# IO.net
KiCad netlist of a schematic drawn in Altium Designer
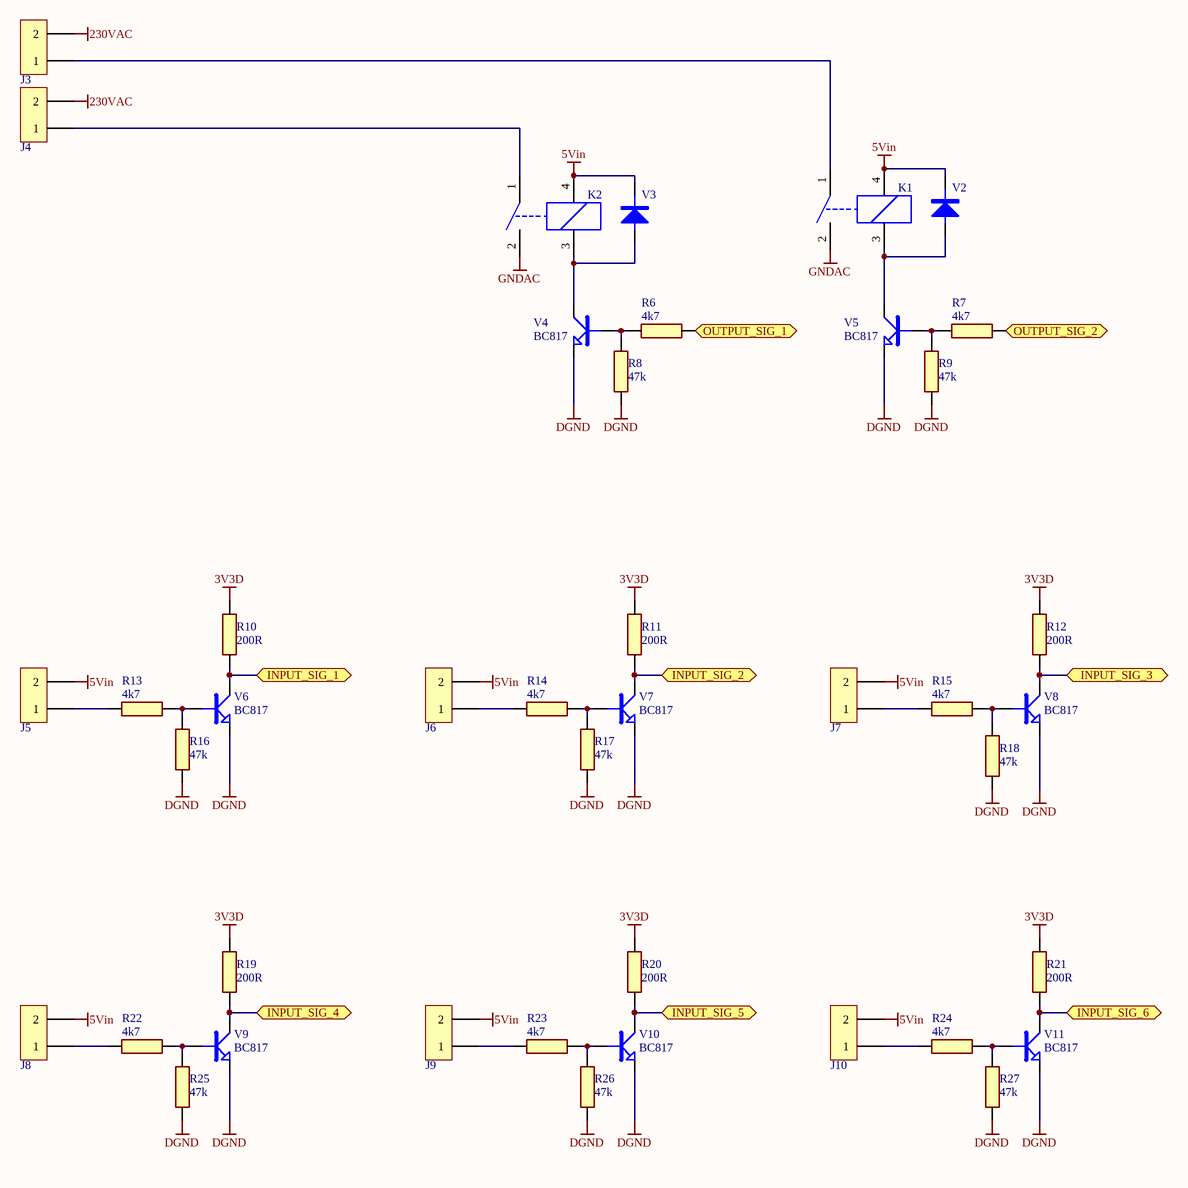
[diagram p0: IO.SchDoc]

(export (version "E")
  (design (tool "Eeschema 10.0.6"))
  (components
    (comp (ref "J3")
      (value "CON2")
      (footprint "CON-MSTB-5.08-2p")
      (description "2 pole connector")
      (libsource (lib "Moj_Lib") (part "CON2"))
    )
    (comp (ref "J4")
      (value "CON2")
      (footprint "CON-MSTB-5.08-2p")
      (description "2 pole connector")
      (libsource (lib "Moj_Lib") (part "CON2"))
    )
    (comp (ref "J5")
      (value "CON2")
      (footprint "CON-MSTB-5.08-2p")
      (description "2 pole connector")
      (libsource (lib "Moj_Lib") (part "CON2"))
    )
    (comp (ref "J6")
      (value "CON2")
      (footprint "CON-MSTB-5.08-2p")
      (description "2 pole connector")
      (libsource (lib "Moj_Lib") (part "CON2"))
    )
    (comp (ref "J7")
      (value "CON2")
      (footprint "CON-MSTB-5.08-2p")
      (description "2 pole connector")
      (libsource (lib "Moj_Lib") (part "CON2"))
    )
    (comp (ref "J8")
      (value "CON2")
      (footprint "CON-MSTB-5.08-2p")
      (description "2 pole connector")
      (libsource (lib "Moj_Lib") (part "CON2"))
    )
    (comp (ref "J9")
      (value "CON2")
      (footprint "CON-MSTB-5.08-2p")
      (description "2 pole connector")
      (libsource (lib "Moj_Lib") (part "CON2"))
    )
    (comp (ref "J10")
      (value "CON2")
      (footprint "CON-MSTB-5.08-2p")
      (description "2 pole connector")
      (libsource (lib "Moj_Lib") (part "CON2"))
    )
    (comp (ref "K1")
      (value "RELAY-HF49FD_012-1H12F")
      (footprint "RELAY-HF49FD_012-1H12F")
      (description "Relay")
      (libsource (lib "Moj_lib") (part "RELAY-HF49FD_012-1H12F"))
    )
    (comp (ref "K2")
      (value "RELAY-HF49FD_012-1H12F")
      (footprint "RELAY-HF49FD_012-1H12F")
      (description "Relay")
      (libsource (lib "Moj_lib") (part "RELAY-HF49FD_012-1H12F"))
    )
    (comp (ref "R6")
      (value "4k7")
      (footprint "RES_0805_SMD")
      (description "0805")
      (libsource (lib "") (part "RES_1"))
    )
    (comp (ref "R7")
      (value "4k7")
      (footprint "RES_0805_SMD")
      (description "0805")
      (libsource (lib "") (part "RES_3"))
    )
    (comp (ref "R8")
      (value "47k")
      (footprint "RES_0805_SMD")
      (description "0805")
      (libsource (lib "") (part "RES_2"))
    )
    (comp (ref "R9")
      (value "47k")
      (footprint "RES_0805_SMD")
      (description "0805")
      (libsource (lib "") (part "RES_2"))
    )
    (comp (ref "R10")
      (value "200R")
      (footprint "RES_0805_SMD")
      (description "0805")
      (libsource (lib "") (part "RES_2"))
    )
    (comp (ref "R11")
      (value "200R")
      (footprint "RES_0805_SMD")
      (description "0805")
      (libsource (lib "") (part "RES_2"))
    )
    (comp (ref "R12")
      (value "200R")
      (footprint "RES_0805_SMD")
      (description "0805")
      (libsource (lib "") (part "RES_2"))
    )
    (comp (ref "R13")
      (value "4k7")
      (footprint "RES_0805_SMD")
      (description "0805")
      (libsource (lib "") (part "RES_1"))
    )
    (comp (ref "R14")
      (value "4k7")
      (footprint "RES_0805_SMD")
      (description "0805")
      (libsource (lib "") (part "RES_1"))
    )
    (comp (ref "R15")
      (value "4k7")
      (footprint "RES_0805_SMD")
      (description "0805")
      (libsource (lib "") (part "RES_1"))
    )
    (comp (ref "R16")
      (value "47k")
      (footprint "RES_0805_SMD")
      (description "0805")
      (libsource (lib "") (part "RES_2"))
    )
    (comp (ref "R17")
      (value "47k")
      (footprint "RES_0805_SMD")
      (description "0805")
      (libsource (lib "Moj_lib") (part "RES"))
    )
    (comp (ref "R18")
      (value "47k")
      (footprint "RES_0805_SMD")
      (description "0805")
      (libsource (lib "") (part "RES_2"))
    )
    (comp (ref "R19")
      (value "200R")
      (footprint "RES_0805_SMD")
      (description "0805")
      (libsource (lib "") (part "RES_2"))
    )
    (comp (ref "R20")
      (value "200R")
      (footprint "RES_0805_SMD")
      (description "0805")
      (libsource (lib "") (part "RES_2"))
    )
    (comp (ref "R21")
      (value "200R")
      (footprint "RES_0805_SMD")
      (description "0805")
      (libsource (lib "") (part "RES_2"))
    )
    (comp (ref "R22")
      (value "4k7")
      (footprint "RES_0805_SMD")
      (description "0805")
      (libsource (lib "") (part "RES_3"))
    )
    (comp (ref "R23")
      (value "4k7")
      (footprint "RES_0805_SMD")
      (description "0805")
      (libsource (lib "") (part "RES_1"))
    )
    (comp (ref "R24")
      (value "4k7")
      (footprint "RES_0805_SMD")
      (description "0805")
      (libsource (lib "") (part "RES_3"))
    )
    (comp (ref "R25")
      (value "47k")
      (footprint "RES_0805_SMD")
      (description "0805")
      (libsource (lib "Moj_lib") (part "RES"))
    )
    (comp (ref "R26")
      (value "47k")
      (footprint "RES_0805_SMD")
      (description "0805")
      (libsource (lib "") (part "RES_2"))
    )
    (comp (ref "R27")
      (value "47k")
      (footprint "RES_0805_SMD")
      (description "0805")
      (libsource (lib "Moj_lib") (part "RES"))
    )
    (comp (ref "V2")
      (value "DIODE")
      (footprint "DIODE-0.4_H")
      (description "Trough hole diode")
      (libsource (lib "ShemaLibrary_IEL") (part "DIODE"))
    )
    (comp (ref "V3")
      (value "DIODE")
      (footprint "DIODE-0.4_H")
      (description "Trough hole diode")
      (libsource (lib "ShemaLibrary_IEL") (part "DIODE"))
    )
    (comp (ref "V4")
      (value "BC817")
      (footprint "SOT-23_P")
      (description "NPN tranzistor BC-817")
      (libsource (lib "ShemaLibrary_IEL") (part "BC817"))
    )
    (comp (ref "V5")
      (value "BC817")
      (footprint "SOT-23_P")
      (description "NPN tranzistor BC-817")
      (libsource (lib "ShemaLibrary_IEL") (part "BC817"))
    )
    (comp (ref "V6")
      (value "BC817")
      (footprint "SOT-23_P")
      (description "NPN tranzistor BC-817")
      (libsource (lib "ShemaLibrary_IEL") (part "BC817"))
    )
    (comp (ref "V7")
      (value "BC817")
      (footprint "SOT-23_P")
      (description "NPN tranzistor BC-817")
      (libsource (lib "ShemaLibrary_IEL") (part "BC817"))
    )
    (comp (ref "V8")
      (value "BC817")
      (footprint "SOT-23_P")
      (description "NPN tranzistor BC-817")
      (libsource (lib "ShemaLibrary_IEL") (part "BC817"))
    )
    (comp (ref "V9")
      (value "BC817")
      (footprint "SOT-23_P")
      (description "NPN tranzistor BC-817")
      (libsource (lib "ShemaLibrary_IEL") (part "BC817"))
    )
    (comp (ref "V10")
      (value "BC817")
      (footprint "SOT-23_P")
      (description "NPN tranzistor BC-817")
      (libsource (lib "ShemaLibrary_IEL") (part "BC817"))
    )
    (comp (ref "V11")
      (value "BC817")
      (footprint "SOT-23_P")
      (description "NPN tranzistor BC-817")
      (libsource (lib "ShemaLibrary_IEL") (part "BC817"))
    )
  )
  (nets
    (net (code "1") (name "/INPUT_SIG_1") (class "Default")
      (node (ref "R10") (pin "1") (pinfunction "1_1") (pintype "passive"))
      (node (ref "V6") (pin "3") (pinfunction "C_3") (pintype "passive"))
    )
    (net (code "2") (name "/INPUT_SIG_2") (class "Default")
      (node (ref "R11") (pin "1") (pinfunction "1_1") (pintype "passive"))
      (node (ref "V7") (pin "3") (pinfunction "C_3") (pintype "passive"))
    )
    (net (code "3") (name "/INPUT_SIG_3") (class "Default")
      (node (ref "R12") (pin "1") (pinfunction "1_1") (pintype "passive"))
      (node (ref "V8") (pin "3") (pinfunction "C_3") (pintype "passive"))
    )
    (net (code "4") (name "/INPUT_SIG_4") (class "Default")
      (node (ref "R19") (pin "1") (pinfunction "1_1") (pintype "passive"))
      (node (ref "V9") (pin "3") (pinfunction "C_3") (pintype "passive"))
    )
    (net (code "5") (name "/INPUT_SIG_5") (class "Default")
      (node (ref "R20") (pin "1") (pinfunction "1_1") (pintype "passive"))
      (node (ref "V10") (pin "3") (pinfunction "C_3") (pintype "passive"))
    )
    (net (code "6") (name "/INPUT_SIG_6") (class "Default")
      (node (ref "R21") (pin "1") (pinfunction "1_1") (pintype "passive"))
      (node (ref "V11") (pin "3") (pinfunction "C_3") (pintype "passive"))
    )
    (net (code "7") (name "/OUTPUT_SIG_1") (class "Default")
      (node (ref "R6") (pin "2") (pinfunction "2_2") (pintype "passive"))
    )
    (net (code "8") (name "/OUTPUT_SIG_2") (class "Default")
      (node (ref "R7") (pin "1") (pinfunction "1_1") (pintype "passive"))
    )
    (net (code "9") (name "3V3D") (class "Default")
      (node (ref "R10") (pin "2") (pinfunction "2_2") (pintype "passive"))
      (node (ref "R11") (pin "2") (pinfunction "2_2") (pintype "passive"))
      (node (ref "R12") (pin "2") (pinfunction "2_2") (pintype "passive"))
      (node (ref "R19") (pin "2") (pinfunction "2_2") (pintype "passive"))
      (node (ref "R20") (pin "2") (pinfunction "2_2") (pintype "passive"))
      (node (ref "R21") (pin "2") (pinfunction "2_2") (pintype "passive"))
    )
    (net (code "10") (name "5Vin") (class "Default")
      (node (ref "J10") (pin "2") (pinfunction "2_2") (pintype "passive"))
      (node (ref "J5") (pin "2") (pinfunction "2_2") (pintype "passive"))
      (node (ref "J6") (pin "2") (pinfunction "2_2") (pintype "passive"))
      (node (ref "J7") (pin "2") (pinfunction "2_2") (pintype "passive"))
      (node (ref "J8") (pin "2") (pinfunction "2_2") (pintype "passive"))
      (node (ref "J9") (pin "2") (pinfunction "2_2") (pintype "passive"))
      (node (ref "K1") (pin "4") (pinfunction "COIL_2_4") (pintype "passive"))
      (node (ref "K2") (pin "4") (pinfunction "COIL_2_4") (pintype "passive"))
      (node (ref "V2") (pin "2") (pinfunction "2_2") (pintype "passive"))
      (node (ref "V3") (pin "2") (pinfunction "2_2") (pintype "passive"))
    )
    (net (code "11") (name "230VAC") (class "Default")
      (node (ref "J3") (pin "2") (pinfunction "2_2") (pintype "passive"))
      (node (ref "J4") (pin "2") (pinfunction "2_2") (pintype "passive"))
    )
    (net (code "12") (name "DGND") (class "Default")
      (node (ref "R16") (pin "1") (pinfunction "1_1") (pintype "passive"))
      (node (ref "R17") (pin "2") (pinfunction "2_2") (pintype "passive"))
      (node (ref "R18") (pin "1") (pinfunction "1_1") (pintype "passive"))
      (node (ref "R25") (pin "2") (pinfunction "2_2") (pintype "passive"))
      (node (ref "R26") (pin "1") (pinfunction "1_1") (pintype "passive"))
      (node (ref "R27") (pin "2") (pinfunction "2_2") (pintype "passive"))
      (node (ref "R8") (pin "1") (pinfunction "1_1") (pintype "passive"))
      (node (ref "R9") (pin "1") (pinfunction "1_1") (pintype "passive"))
      (node (ref "V10") (pin "2") (pinfunction "E_2") (pintype "passive"))
      (node (ref "V11") (pin "2") (pinfunction "E_2") (pintype "passive"))
      (node (ref "V4") (pin "2") (pinfunction "E_2") (pintype "passive"))
      (node (ref "V5") (pin "2") (pinfunction "E_2") (pintype "passive"))
      (node (ref "V6") (pin "2") (pinfunction "E_2") (pintype "passive"))
      (node (ref "V7") (pin "2") (pinfunction "E_2") (pintype "passive"))
      (node (ref "V8") (pin "2") (pinfunction "E_2") (pintype "passive"))
      (node (ref "V9") (pin "2") (pinfunction "E_2") (pintype "passive"))
    )
    (net (code "13") (name "GNDAC") (class "Default")
      (node (ref "K1") (pin "2") (pinfunction "NO_2") (pintype "passive"))
      (node (ref "K2") (pin "2") (pinfunction "NO_2") (pintype "passive"))
    )
    (net (code "14") (name "Net-(J5-Pad1)") (class "Default")
      (node (ref "J5") (pin "1") (pinfunction "1_1") (pintype "passive"))
      (node (ref "R13") (pin "1") (pinfunction "1_1") (pintype "passive"))
    )
    (net (code "15") (name "Net-(J6-Pad1)") (class "Default")
      (node (ref "J6") (pin "1") (pinfunction "1_1") (pintype "passive"))
      (node (ref "R14") (pin "1") (pinfunction "1_1") (pintype "passive"))
    )
    (net (code "16") (name "Net-(J7-Pad1)") (class "Default")
      (node (ref "J7") (pin "1") (pinfunction "1_1") (pintype "passive"))
      (node (ref "R15") (pin "1") (pinfunction "1_1") (pintype "passive"))
    )
    (net (code "17") (name "Net-(J8-Pad1)") (class "Default")
      (node (ref "J8") (pin "1") (pinfunction "1_1") (pintype "passive"))
      (node (ref "R22") (pin "2") (pinfunction "2_2") (pintype "passive"))
    )
    (net (code "18") (name "Net-(J9-Pad1)") (class "Default")
      (node (ref "J9") (pin "1") (pinfunction "1_1") (pintype "passive"))
      (node (ref "R23") (pin "1") (pinfunction "1_1") (pintype "passive"))
    )
    (net (code "19") (name "Net-(J10-Pad1)") (class "Default")
      (node (ref "J10") (pin "1") (pinfunction "1_1") (pintype "passive"))
      (node (ref "R24") (pin "2") (pinfunction "2_2") (pintype "passive"))
    )
    (net (code "20") (name "Net-(K1-COIL_1)") (class "Default")
      (node (ref "K1") (pin "3") (pinfunction "COIL_1_3") (pintype "passive"))
      (node (ref "V2") (pin "1") (pinfunction "1_1") (pintype "passive"))
      (node (ref "V5") (pin "3") (pinfunction "C_3") (pintype "passive"))
    )
    (net (code "21") (name "Net-(K1-COM)") (class "Default")
      (node (ref "J3") (pin "1") (pinfunction "1_1") (pintype "passive"))
      (node (ref "K1") (pin "1") (pinfunction "COM_1") (pintype "passive"))
    )
    (net (code "22") (name "Net-(K2-COIL_1)") (class "Default")
      (node (ref "K2") (pin "3") (pinfunction "COIL_1_3") (pintype "passive"))
      (node (ref "V3") (pin "1") (pinfunction "1_1") (pintype "passive"))
      (node (ref "V4") (pin "3") (pinfunction "C_3") (pintype "passive"))
    )
    (net (code "23") (name "Net-(K2-COM)") (class "Default")
      (node (ref "J4") (pin "1") (pinfunction "1_1") (pintype "passive"))
      (node (ref "K2") (pin "1") (pinfunction "COM_1") (pintype "passive"))
    )
    (net (code "24") (name "Net-(V4-B)") (class "Default")
      (node (ref "R6") (pin "1") (pinfunction "1_1") (pintype "passive"))
      (node (ref "R8") (pin "2") (pinfunction "2_2") (pintype "passive"))
      (node (ref "V4") (pin "1") (pinfunction "B_1") (pintype "passive"))
    )
    (net (code "25") (name "Net-(V5-B)") (class "Default")
      (node (ref "R7") (pin "2") (pinfunction "2_2") (pintype "passive"))
      (node (ref "R9") (pin "2") (pinfunction "2_2") (pintype "passive"))
      (node (ref "V5") (pin "1") (pinfunction "B_1") (pintype "passive"))
    )
    (net (code "26") (name "Net-(V6-B)") (class "Default")
      (node (ref "R13") (pin "2") (pinfunction "2_2") (pintype "passive"))
      (node (ref "R16") (pin "2") (pinfunction "2_2") (pintype "passive"))
      (node (ref "V6") (pin "1") (pinfunction "B_1") (pintype "passive"))
    )
    (net (code "27") (name "Net-(V7-B)") (class "Default")
      (node (ref "R14") (pin "2") (pinfunction "2_2") (pintype "passive"))
      (node (ref "R17") (pin "1") (pinfunction "1_1") (pintype "passive"))
      (node (ref "V7") (pin "1") (pinfunction "B_1") (pintype "passive"))
    )
    (net (code "28") (name "Net-(V8-B)") (class "Default")
      (node (ref "R15") (pin "2") (pinfunction "2_2") (pintype "passive"))
      (node (ref "R18") (pin "2") (pinfunction "2_2") (pintype "passive"))
      (node (ref "V8") (pin "1") (pinfunction "B_1") (pintype "passive"))
    )
    (net (code "29") (name "Net-(V9-B)") (class "Default")
      (node (ref "R22") (pin "1") (pinfunction "1_1") (pintype "passive"))
      (node (ref "R25") (pin "1") (pinfunction "1_1") (pintype "passive"))
      (node (ref "V9") (pin "1") (pinfunction "B_1") (pintype "passive"))
    )
    (net (code "30") (name "Net-(V10-B)") (class "Default")
      (node (ref "R23") (pin "2") (pinfunction "2_2") (pintype "passive"))
      (node (ref "R26") (pin "2") (pinfunction "2_2") (pintype "passive"))
      (node (ref "V10") (pin "1") (pinfunction "B_1") (pintype "passive"))
    )
    (net (code "31") (name "Net-(V11-B)") (class "Default")
      (node (ref "R24") (pin "1") (pinfunction "1_1") (pintype "passive"))
      (node (ref "R27") (pin "1") (pinfunction "1_1") (pintype "passive"))
      (node (ref "V11") (pin "1") (pinfunction "B_1") (pintype "passive"))
    )
  )
)
